# schematicEagle.net
KiCad netlist of a schematic drawn in EAGLE
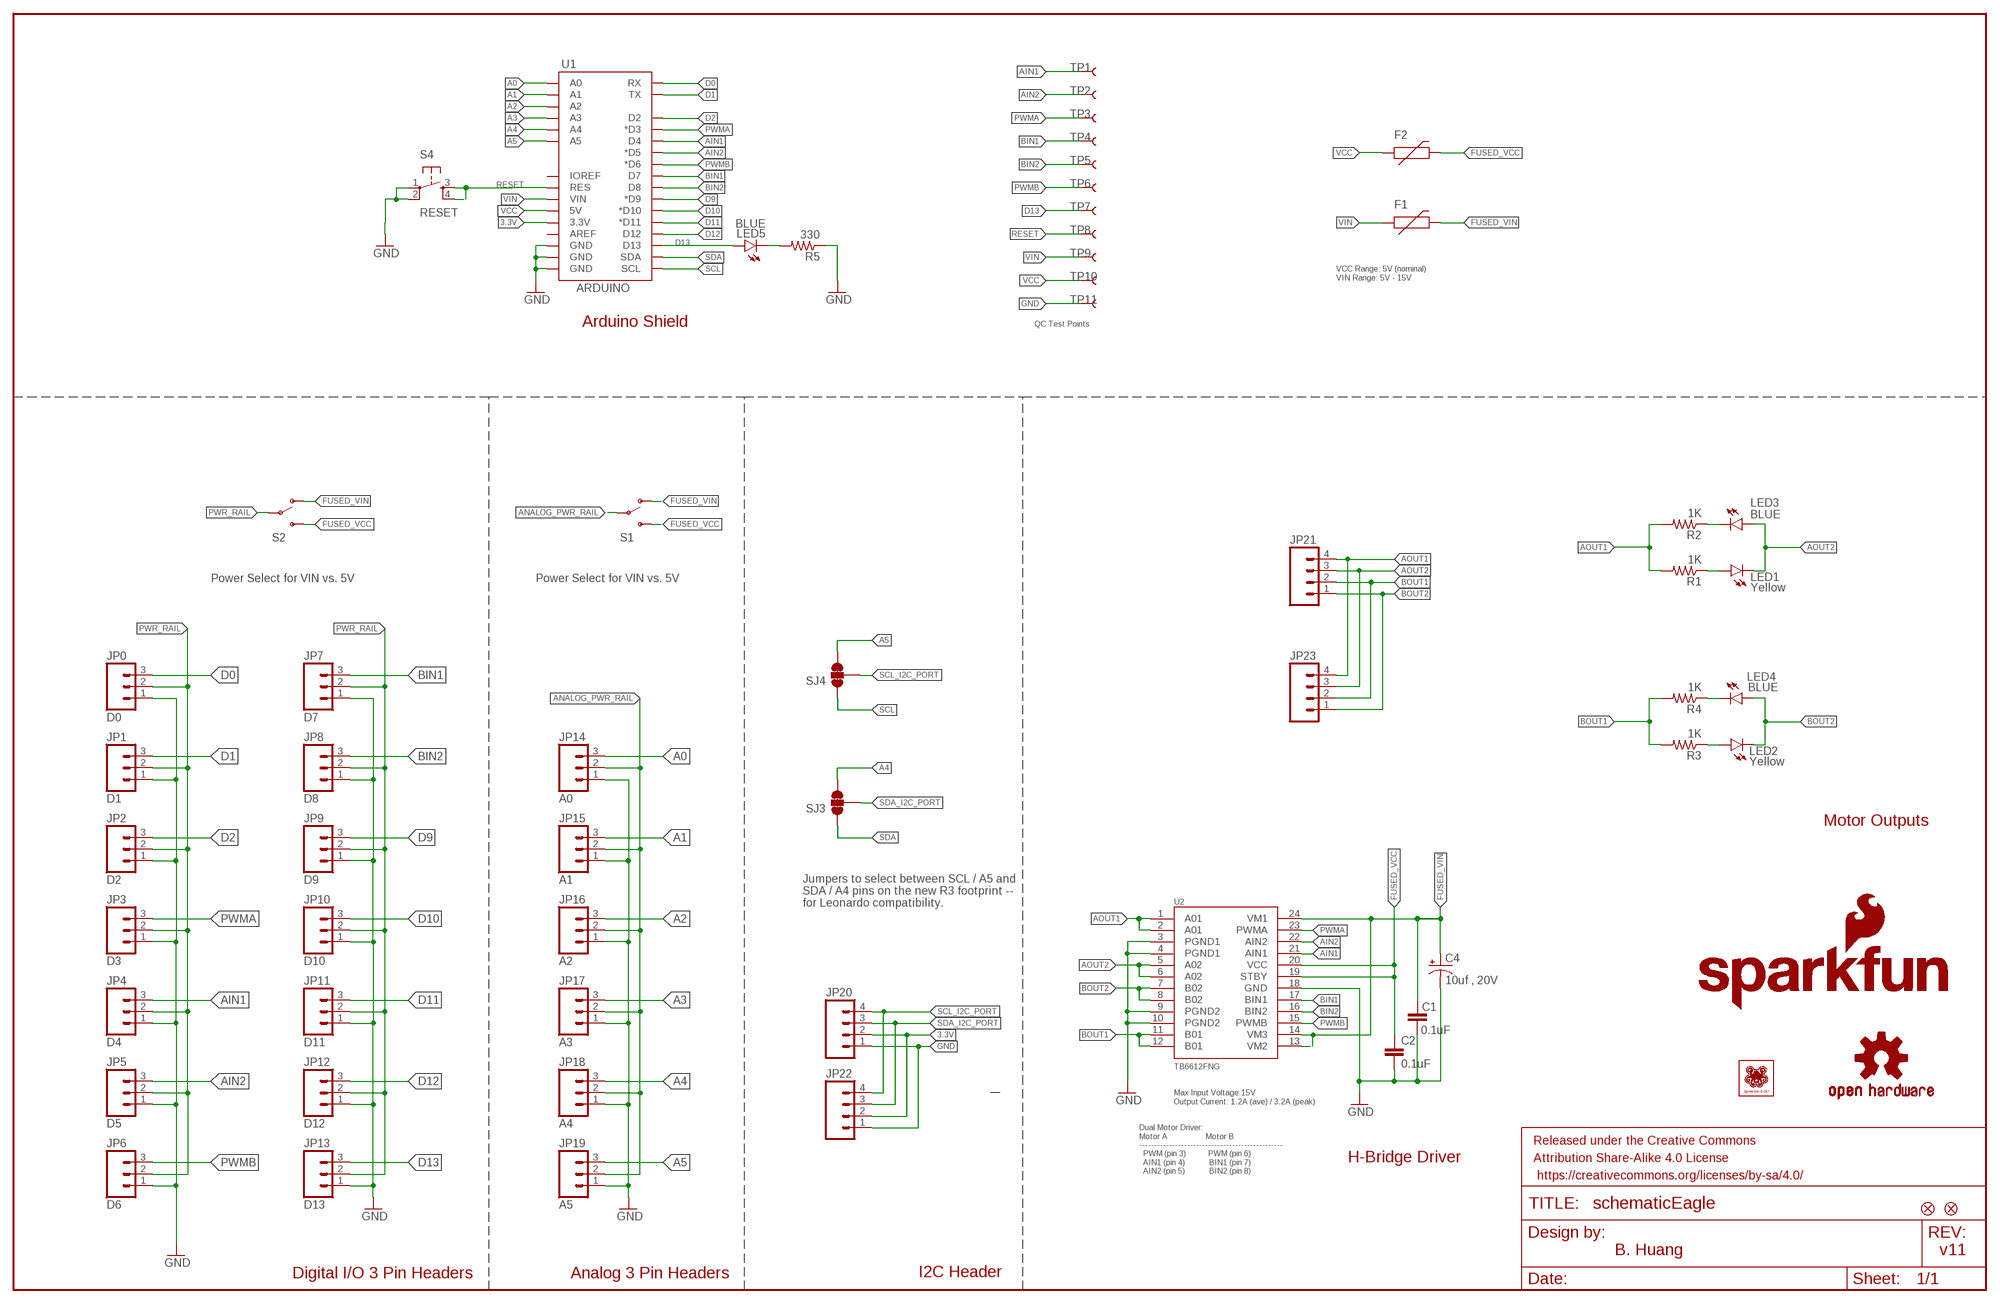
[diagram p0: schematic, sheet 1]

(export (version "E")
  (design (tool "Eeschema 10.0.6"))
  (components
    (comp (ref "C1")
      (value "0.1uF")
      (footprint "eagle-import:0603-CAP")
      (libsource (lib "eagle-import") (part "0.1UF-25V-5%(0603)"))
    )
    (comp (ref "C2")
      (value "0.1uF")
      (footprint "eagle-import:0603-CAP")
      (libsource (lib "eagle-import") (part "0.1UF-25V-5%(0603)"))
    )
    (comp (ref "C4")
      (value "10uf , 20V")
      (footprint "eagle-import:EIA3528")
      (libsource (lib "eagle-import") (part "10UF-20V-10%(TANT)"))
    )
    (comp (ref "F1")
      (value "PTCSMD")
      (footprint "eagle-import:PTC-1206")
      (libsource (lib "eagle-import") (part "PTCSMD"))
    )
    (comp (ref "F2")
      (value "PTCSMD")
      (footprint "eagle-import:PTC-1206")
      (libsource (lib "eagle-import") (part "PTCSMD"))
    )
    (comp (ref "FID1")
      (value "FIDUCIAL1X2")
      (footprint "eagle-import:FIDUCIAL-1X2")
      (libsource (lib "eagle-import") (part "FIDUCIAL1X2"))
    )
    (comp (ref "FID2")
      (value "FIDUCIAL1X2")
      (footprint "eagle-import:FIDUCIAL-1X2")
      (libsource (lib "eagle-import") (part "FIDUCIAL1X2"))
    )
    (comp (ref "FRAME2")
      (value "FRAME-LEDGER")
      (footprint "eagle-import:CREATIVE_COMMONS")
      (libsource (lib "eagle-import") (part "FRAME-LEDGER"))
    )
    (comp (ref "JP0")
      (value "D0")
      (footprint "eagle-import:1X03_LOCK")
      (libsource (lib "eagle-import") (part "M03LOCK"))
    )
    (comp (ref "JP1")
      (value "D1")
      (footprint "eagle-import:1X03_LOCK")
      (libsource (lib "eagle-import") (part "M03LOCK"))
    )
    (comp (ref "JP2")
      (value "D2")
      (footprint "eagle-import:1X03_LOCK")
      (libsource (lib "eagle-import") (part "M03LOCK"))
    )
    (comp (ref "JP3")
      (value "D3")
      (footprint "eagle-import:1X03_LOCK")
      (libsource (lib "eagle-import") (part "M03LOCK"))
    )
    (comp (ref "JP4")
      (value "D4")
      (footprint "eagle-import:1X03_LOCK")
      (libsource (lib "eagle-import") (part "M03LOCK"))
    )
    (comp (ref "JP5")
      (value "D5")
      (footprint "eagle-import:1X03_LOCK")
      (libsource (lib "eagle-import") (part "M03LOCK"))
    )
    (comp (ref "JP6")
      (value "D6")
      (footprint "eagle-import:1X03_LOCK")
      (libsource (lib "eagle-import") (part "M03LOCK"))
    )
    (comp (ref "JP7")
      (value "D7")
      (footprint "eagle-import:1X03_LOCK")
      (libsource (lib "eagle-import") (part "M03LOCK"))
    )
    (comp (ref "JP8")
      (value "D8")
      (footprint "eagle-import:1X03_LOCK")
      (libsource (lib "eagle-import") (part "M03LOCK"))
    )
    (comp (ref "JP9")
      (value "D9")
      (footprint "eagle-import:1X03_LOCK")
      (libsource (lib "eagle-import") (part "M03LOCK"))
    )
    (comp (ref "JP10")
      (value "D10")
      (footprint "eagle-import:1X03_LOCK")
      (libsource (lib "eagle-import") (part "M03LOCK"))
    )
    (comp (ref "JP11")
      (value "D11")
      (footprint "eagle-import:1X03_LOCK")
      (libsource (lib "eagle-import") (part "M03LOCK"))
    )
    (comp (ref "JP12")
      (value "D12")
      (footprint "eagle-import:1X03_LOCK")
      (libsource (lib "eagle-import") (part "M03LOCK"))
    )
    (comp (ref "JP13")
      (value "D13")
      (footprint "eagle-import:1X03_LOCK")
      (libsource (lib "eagle-import") (part "M03LOCK"))
    )
    (comp (ref "JP14")
      (value "A0")
      (footprint "eagle-import:1X03_LOCK")
      (libsource (lib "eagle-import") (part "M03LOCK"))
    )
    (comp (ref "JP15")
      (value "A1")
      (footprint "eagle-import:1X03_LOCK")
      (libsource (lib "eagle-import") (part "M03LOCK"))
    )
    (comp (ref "JP16")
      (value "A2")
      (footprint "eagle-import:1X03_LOCK")
      (libsource (lib "eagle-import") (part "M03LOCK"))
    )
    (comp (ref "JP17")
      (value "A3")
      (footprint "eagle-import:1X03_LOCK")
      (libsource (lib "eagle-import") (part "M03LOCK"))
    )
    (comp (ref "JP18")
      (value "A4")
      (footprint "eagle-import:1X03_LOCK")
      (libsource (lib "eagle-import") (part "M03LOCK"))
    )
    (comp (ref "JP19")
      (value "A5")
      (footprint "eagle-import:1X03_LOCK")
      (libsource (lib "eagle-import") (part "M03LOCK"))
    )
    (comp (ref "JP20")
      (value "M04PTH")
      (footprint "eagle-import:1X04")
      (libsource (lib "eagle-import") (part "M04PTH"))
    )
    (comp (ref "JP21")
      (value "M04PTH")
      (footprint "eagle-import:1X04")
      (libsource (lib "eagle-import") (part "M04PTH"))
    )
    (comp (ref "JP22")
      (value "M04LOCK")
      (footprint "eagle-import:1X04_LOCK")
      (libsource (lib "eagle-import") (part "M04LOCK"))
    )
    (comp (ref "JP23")
      (value "M04LOCK")
      (footprint "eagle-import:1X04_LOCK")
      (libsource (lib "eagle-import") (part "M04LOCK"))
    )
    (comp (ref "LED1")
      (value "Yellow")
      (footprint "eagle-import:LED-0603")
      (libsource (lib "eagle-import") (part "LED-YELLOW0603"))
    )
    (comp (ref "LED2")
      (value "Yellow")
      (footprint "eagle-import:LED-0603")
      (libsource (lib "eagle-import") (part "LED-YELLOW0603"))
    )
    (comp (ref "LED3")
      (value "BLUE")
      (footprint "eagle-import:LED-0603")
      (libsource (lib "eagle-import") (part "LED-BLUE0603"))
    )
    (comp (ref "LED4")
      (value "BLUE")
      (footprint "eagle-import:LED-0603")
      (libsource (lib "eagle-import") (part "LED-BLUE0603"))
    )
    (comp (ref "LED5")
      (value "BLUE")
      (footprint "eagle-import:LED-0603")
      (libsource (lib "eagle-import") (part "LED-BLUE0603"))
    )
    (comp (ref "LOGO1")
      (value "OSHW-LOGOM")
      (footprint "eagle-import:OSHW-LOGO-M")
      (libsource (lib "eagle-import") (part "OSHW-LOGOM"))
    )
    (comp (ref "LOGO2")
      (value "SFE_LOGO_NAME_FLAME.1_INCH")
      (footprint "eagle-import:SFE_LOGO_NAME_FLAME_.1")
      (libsource (lib "eagle-import") (part "SFE_LOGO_NAME_FLAME.1_INCH"))
    )
    (comp (ref "LOGO3")
      (value "SFE_LOGO_FLAME.2COP")
      (footprint "eagle-import:SFE_LOGO_FLAME_COPPER_.2")
      (libsource (lib "eagle-import") (part "SFE_LOGO_FLAME.2COP"))
    )
    (comp (ref "LOGO4")
      (value "SFE_LOGO_NAME_FLAME.1_INCH")
      (footprint "eagle-import:SFE_LOGO_NAME_FLAME_.1")
      (libsource (lib "eagle-import") (part "SFE_LOGO_NAME_FLAME.1_INCH"))
    )
    (comp (ref "R1")
      (value "1K")
      (footprint "eagle-import:0603-RES")
      (libsource (lib "eagle-import") (part "1KOHM-1/10W-1%(0603)"))
    )
    (comp (ref "R2")
      (value "1K")
      (footprint "eagle-import:0603-RES")
      (libsource (lib "eagle-import") (part "1KOHM-1/10W-1%(0603)"))
    )
    (comp (ref "R3")
      (value "1K")
      (footprint "eagle-import:0603-RES")
      (libsource (lib "eagle-import") (part "1KOHM-1/10W-1%(0603)"))
    )
    (comp (ref "R4")
      (value "1K")
      (footprint "eagle-import:0603-RES")
      (libsource (lib "eagle-import") (part "1KOHM-1/10W-1%(0603)"))
    )
    (comp (ref "R5")
      (value "330")
      (footprint "eagle-import:0603-RES")
      (libsource (lib "eagle-import") (part "330OHM1/10W1%(0603)"))
    )
    (comp (ref "S1")
      (value "SWITCH-SPDTSMD")
      (footprint "eagle-import:AYZ0202")
      (libsource (lib "eagle-import") (part "SWITCH-SPDTSMD"))
    )
    (comp (ref "S2")
      (value "SWITCH-SPDTSMD")
      (footprint "eagle-import:AYZ0202")
      (libsource (lib "eagle-import") (part "SWITCH-SPDTSMD"))
    )
    (comp (ref "S4")
      (value "RESET")
      (footprint "eagle-import:TACTILE-SWITCH-SMD")
      (libsource (lib "eagle-import") (part "TAC_SWITCHSMD"))
    )
    (comp (ref "SJ3")
      (value "JUMPER-PAD-3-NC_BY_TRACE")
      (footprint "eagle-import:PAD-JUMPER-3-3OF3_NC_BY_TRACE_YES_SILK_FULL_BOX")
      (libsource (lib "eagle-import") (part "JUMPER-PAD-3-NC_BY_TRACE"))
    )
    (comp (ref "SJ4")
      (value "JUMPER-PAD-3-NC_BY_TRACE")
      (footprint "eagle-import:PAD-JUMPER-3-3OF3_NC_BY_TRACE_YES_SILK_FULL_BOX")
      (libsource (lib "eagle-import") (part "JUMPER-PAD-3-NC_BY_TRACE"))
    )
    (comp (ref "TP1")
      (value "TEST-POINT3X5")
      (footprint "eagle-import:PAD.03X.05")
      (libsource (lib "eagle-import") (part "TEST-POINT3X5"))
    )
    (comp (ref "TP2")
      (value "TEST-POINT3X5")
      (footprint "eagle-import:PAD.03X.05")
      (libsource (lib "eagle-import") (part "TEST-POINT3X5"))
    )
    (comp (ref "TP3")
      (value "TEST-POINT3X5")
      (footprint "eagle-import:PAD.03X.05")
      (libsource (lib "eagle-import") (part "TEST-POINT3X5"))
    )
    (comp (ref "TP4")
      (value "TEST-POINT3X5")
      (footprint "eagle-import:PAD.03X.05")
      (libsource (lib "eagle-import") (part "TEST-POINT3X5"))
    )
    (comp (ref "TP5")
      (value "TEST-POINT3X5")
      (footprint "eagle-import:PAD.03X.05")
      (libsource (lib "eagle-import") (part "TEST-POINT3X5"))
    )
    (comp (ref "TP6")
      (value "TEST-POINT3X5")
      (footprint "eagle-import:PAD.03X.05")
      (libsource (lib "eagle-import") (part "TEST-POINT3X5"))
    )
    (comp (ref "TP7")
      (value "TEST-POINT3X5")
      (footprint "eagle-import:PAD.03X.05")
      (libsource (lib "eagle-import") (part "TEST-POINT3X5"))
    )
    (comp (ref "TP8")
      (value "TEST-POINT3X5")
      (footprint "eagle-import:PAD.03X.05")
      (libsource (lib "eagle-import") (part "TEST-POINT3X5"))
    )
    (comp (ref "TP9")
      (value "TEST-POINT3X5")
      (footprint "eagle-import:PAD.03X.05")
      (libsource (lib "eagle-import") (part "TEST-POINT3X5"))
    )
    (comp (ref "TP10")
      (value "TEST-POINT3X5")
      (footprint "eagle-import:PAD.03X.05")
      (libsource (lib "eagle-import") (part "TEST-POINT3X5"))
    )
    (comp (ref "TP11")
      (value "TEST-POINT3X5")
      (footprint "eagle-import:PAD.03X.05")
      (libsource (lib "eagle-import") (part "TEST-POINT3X5"))
    )
    (comp (ref "U$1")
      (value "SFE_LUDUSSFE_LUDUS-M")
      (footprint "eagle-import:SFE_LUDUS-M")
      (libsource (lib "eagle-import") (part "SFE_LUDUSSFE_LUDUS-M"))
    )
    (comp (ref "U1")
      (value "ARDUINO")
      (footprint "eagle-import:UNO_R3_SHIELD_NOLABELS_LOCK")
      (libsource (lib "eagle-import") (part "ARDUINO_R3_SHIELDUNO_R3_SHIELD_NOLABELS_LOCK"))
    )
    (comp (ref "U2")
      (value "TB6612FNG")
      (footprint "eagle-import:SSOP24")
      (libsource (lib "eagle-import") (part "TB6612FNG"))
    )
  )
  (nets
    (net (code "1") (name "3.3V") (class "Default")
      (node (ref "JP20") (pin "2") (pinfunction "2_2") (pintype "passive"))
      (node (ref "JP22") (pin "2") (pinfunction "2_2") (pintype "passive"))
      (node (ref "U1") (pin "3.3V") (pinfunction "3.3V_3.3V") (pintype "bidirectional"))
    )
    (net (code "2") (name "A0") (class "Default")
      (node (ref "JP14") (pin "3") (pinfunction "3_3") (pintype "passive"))
      (node (ref "U1") (pin "A0") (pinfunction "A0_A0") (pintype "bidirectional"))
    )
    (net (code "3") (name "A1") (class "Default")
      (node (ref "JP15") (pin "3") (pinfunction "3_3") (pintype "passive"))
      (node (ref "U1") (pin "A1") (pinfunction "A1_A1") (pintype "bidirectional"))
    )
    (net (code "4") (name "A2") (class "Default")
      (node (ref "JP16") (pin "3") (pinfunction "3_3") (pintype "passive"))
      (node (ref "U1") (pin "A2") (pinfunction "A2_A2") (pintype "bidirectional"))
    )
    (net (code "5") (name "A3") (class "Default")
      (node (ref "JP17") (pin "3") (pinfunction "3_3") (pintype "passive"))
      (node (ref "U1") (pin "A3") (pinfunction "A3_A3") (pintype "bidirectional"))
    )
    (net (code "6") (name "A4") (class "Default")
      (node (ref "JP18") (pin "3") (pinfunction "3_3") (pintype "passive"))
      (node (ref "SJ3") (pin "3") (pinfunction "3_3") (pintype "passive"))
      (node (ref "U1") (pin "A4") (pinfunction "A4_A4") (pintype "bidirectional"))
    )
    (net (code "7") (name "A5") (class "Default")
      (node (ref "JP19") (pin "3") (pinfunction "3_3") (pintype "passive"))
      (node (ref "SJ4") (pin "3") (pinfunction "3_3") (pintype "passive"))
      (node (ref "U1") (pin "A5") (pinfunction "A5_A5") (pintype "bidirectional"))
    )
    (net (code "8") (name "AIN1") (class "Default")
      (node (ref "JP4") (pin "3") (pinfunction "3_3") (pintype "passive"))
      (node (ref "TP1") (pin "P$1") (pinfunction "1_P$1") (pintype "bidirectional"))
      (node (ref "U1") (pin "D4") (pinfunction "D4_D4") (pintype "bidirectional"))
      (node (ref "U2") (pin "21") (pinfunction "AIN1_21") (pintype "bidirectional"))
    )
    (net (code "9") (name "AIN2") (class "Default")
      (node (ref "JP5") (pin "3") (pinfunction "3_3") (pintype "passive"))
      (node (ref "TP2") (pin "P$1") (pinfunction "1_P$1") (pintype "bidirectional"))
      (node (ref "U1") (pin "D5") (pinfunction "*D5_D5") (pintype "bidirectional"))
      (node (ref "U2") (pin "22") (pinfunction "AIN2_22") (pintype "bidirectional"))
    )
    (net (code "10") (name "ANALOG_PWR_RAIL") (class "Default")
      (node (ref "JP14") (pin "2") (pinfunction "2_2") (pintype "passive"))
      (node (ref "JP15") (pin "2") (pinfunction "2_2") (pintype "passive"))
      (node (ref "JP16") (pin "2") (pinfunction "2_2") (pintype "passive"))
      (node (ref "JP17") (pin "2") (pinfunction "2_2") (pintype "passive"))
      (node (ref "JP18") (pin "2") (pinfunction "2_2") (pintype "passive"))
      (node (ref "JP19") (pin "2") (pinfunction "2_2") (pintype "passive"))
      (node (ref "S1") (pin "2") (pinfunction "P_2") (pintype "passive"))
    )
    (net (code "11") (name "AOUT1") (class "Default")
      (node (ref "JP21") (pin "4") (pinfunction "4_4") (pintype "passive"))
      (node (ref "JP23") (pin "4") (pinfunction "4_4") (pintype "passive"))
      (node (ref "R1") (pin "2") (pinfunction "2_2") (pintype "passive"))
      (node (ref "R2") (pin "2") (pinfunction "2_2") (pintype "passive"))
      (node (ref "U2") (pin "1") (pinfunction "A01_1") (pintype "bidirectional"))
      (node (ref "U2") (pin "2") (pinfunction "A01_2") (pintype "bidirectional"))
    )
    (net (code "12") (name "AOUT2") (class "Default")
      (node (ref "JP21") (pin "3") (pinfunction "3_3") (pintype "passive"))
      (node (ref "JP23") (pin "3") (pinfunction "3_3") (pintype "passive"))
      (node (ref "LED1") (pin "C") (pinfunction "C_C") (pintype "passive"))
      (node (ref "LED3") (pin "A") (pinfunction "A_A") (pintype "passive"))
      (node (ref "U2") (pin "5") (pinfunction "A02_5") (pintype "bidirectional"))
      (node (ref "U2") (pin "6") (pinfunction "A02_6") (pintype "bidirectional"))
    )
    (net (code "13") (name "BIN1") (class "Default")
      (node (ref "JP7") (pin "3") (pinfunction "3_3") (pintype "passive"))
      (node (ref "TP4") (pin "P$1") (pinfunction "1_P$1") (pintype "bidirectional"))
      (node (ref "U1") (pin "D7") (pinfunction "D7_D7") (pintype "bidirectional"))
      (node (ref "U2") (pin "17") (pinfunction "BIN1_17") (pintype "bidirectional"))
    )
    (net (code "14") (name "BIN2") (class "Default")
      (node (ref "JP8") (pin "3") (pinfunction "3_3") (pintype "passive"))
      (node (ref "TP5") (pin "P$1") (pinfunction "1_P$1") (pintype "bidirectional"))
      (node (ref "U1") (pin "D8") (pinfunction "D8_D8") (pintype "bidirectional"))
      (node (ref "U2") (pin "16") (pinfunction "BIN2_16") (pintype "bidirectional"))
    )
    (net (code "15") (name "BOUT1") (class "Default")
      (node (ref "JP21") (pin "2") (pinfunction "2_2") (pintype "passive"))
      (node (ref "JP23") (pin "2") (pinfunction "2_2") (pintype "passive"))
      (node (ref "R3") (pin "2") (pinfunction "2_2") (pintype "passive"))
      (node (ref "R4") (pin "2") (pinfunction "2_2") (pintype "passive"))
      (node (ref "U2") (pin "11") (pinfunction "B01_11") (pintype "bidirectional"))
      (node (ref "U2") (pin "12") (pinfunction "B01_12") (pintype "bidirectional"))
    )
    (net (code "16") (name "BOUT2") (class "Default")
      (node (ref "JP21") (pin "1") (pinfunction "1_1") (pintype "passive"))
      (node (ref "JP23") (pin "1") (pinfunction "1_1") (pintype "passive"))
      (node (ref "LED2") (pin "C") (pinfunction "C_C") (pintype "passive"))
      (node (ref "LED4") (pin "A") (pinfunction "A_A") (pintype "passive"))
      (node (ref "U2") (pin "7") (pinfunction "B02_7") (pintype "bidirectional"))
      (node (ref "U2") (pin "8") (pinfunction "B02_8") (pintype "bidirectional"))
    )
    (net (code "17") (name "D0") (class "Default")
      (node (ref "JP0") (pin "3") (pinfunction "3_3") (pintype "passive"))
      (node (ref "U1") (pin "RX") (pinfunction "RX_RX") (pintype "bidirectional"))
    )
    (net (code "18") (name "D1") (class "Default")
      (node (ref "JP1") (pin "3") (pinfunction "3_3") (pintype "passive"))
      (node (ref "U1") (pin "TX") (pinfunction "TX_TX") (pintype "bidirectional"))
    )
    (net (code "19") (name "D2") (class "Default")
      (node (ref "JP2") (pin "3") (pinfunction "3_3") (pintype "passive"))
      (node (ref "U1") (pin "D2") (pinfunction "D2_D2") (pintype "bidirectional"))
    )
    (net (code "20") (name "D9") (class "Default")
      (node (ref "JP9") (pin "3") (pinfunction "3_3") (pintype "passive"))
      (node (ref "U1") (pin "D9") (pinfunction "*D9_D9") (pintype "bidirectional"))
    )
    (net (code "21") (name "D10") (class "Default")
      (node (ref "JP10") (pin "3") (pinfunction "3_3") (pintype "passive"))
      (node (ref "U1") (pin "D10") (pinfunction "*D10_D10") (pintype "bidirectional"))
    )
    (net (code "22") (name "D11") (class "Default")
      (node (ref "JP11") (pin "3") (pinfunction "3_3") (pintype "passive"))
      (node (ref "U1") (pin "D11") (pinfunction "*D11_D11") (pintype "bidirectional"))
    )
    (net (code "23") (name "D12") (class "Default")
      (node (ref "JP12") (pin "3") (pinfunction "3_3") (pintype "passive"))
      (node (ref "U1") (pin "D12") (pinfunction "D12_D12") (pintype "bidirectional"))
    )
    (net (code "24") (name "D13") (class "Default")
      (node (ref "JP13") (pin "3") (pinfunction "3_3") (pintype "passive"))
      (node (ref "LED5") (pin "A") (pinfunction "A_A") (pintype "passive"))
      (node (ref "TP7") (pin "P$1") (pinfunction "1_P$1") (pintype "bidirectional"))
      (node (ref "U1") (pin "D13") (pinfunction "D13_D13") (pintype "bidirectional"))
    )
    (net (code "25") (name "FUSED_VCC") (class "Default")
      (node (ref "C2") (pin "1") (pinfunction "1_1") (pintype "passive"))
      (node (ref "F2") (pin "2") (pinfunction "2_2") (pintype "bidirectional"))
      (node (ref "S1") (pin "3") (pinfunction "S_3") (pintype "passive"))
      (node (ref "S2") (pin "3") (pinfunction "S_3") (pintype "passive"))
      (node (ref "U2") (pin "19") (pinfunction "STBY_19") (pintype "bidirectional"))
      (node (ref "U2") (pin "20") (pinfunction "VCC_20") (pintype "bidirectional"))
    )
    (net (code "26") (name "FUSED_VIN") (class "Default")
      (node (ref "C1") (pin "1") (pinfunction "1_1") (pintype "passive"))
      (node (ref "C4") (pin "A") (pinfunction "+_A") (pintype "passive"))
      (node (ref "F1") (pin "2") (pinfunction "2_2") (pintype "bidirectional"))
      (node (ref "S1") (pin "1") (pinfunction "O_1") (pintype "passive"))
      (node (ref "S2") (pin "1") (pinfunction "O_1") (pintype "passive"))
      (node (ref "U2") (pin "13") (pinfunction "VM2_13") (pintype "bidirectional"))
      (node (ref "U2") (pin "14") (pinfunction "VM3_14") (pintype "bidirectional"))
      (node (ref "U2") (pin "24") (pinfunction "VM1_24") (pintype "bidirectional"))
    )
    (net (code "27") (name "GND") (class "Default")
      (node (ref "C1") (pin "2") (pinfunction "2_2") (pintype "passive"))
      (node (ref "C2") (pin "2") (pinfunction "2_2") (pintype "passive"))
      (node (ref "C4") (pin "C") (pinfunction "-_C") (pintype "passive"))
      (node (ref "JP0") (pin "1") (pinfunction "1_1") (pintype "passive"))
      (node (ref "JP1") (pin "1") (pinfunction "1_1") (pintype "passive"))
      (node (ref "JP10") (pin "1") (pinfunction "1_1") (pintype "passive"))
      (node (ref "JP11") (pin "1") (pinfunction "1_1") (pintype "passive"))
      (node (ref "JP12") (pin "1") (pinfunction "1_1") (pintype "passive"))
      (node (ref "JP13") (pin "1") (pinfunction "1_1") (pintype "passive"))
      (node (ref "JP14") (pin "1") (pinfunction "1_1") (pintype "passive"))
      (node (ref "JP15") (pin "1") (pinfunction "1_1") (pintype "passive"))
      (node (ref "JP16") (pin "1") (pinfunction "1_1") (pintype "passive"))
      (node (ref "JP17") (pin "1") (pinfunction "1_1") (pintype "passive"))
      (node (ref "JP18") (pin "1") (pinfunction "1_1") (pintype "passive"))
      (node (ref "JP19") (pin "1") (pinfunction "1_1") (pintype "passive"))
      (node (ref "JP2") (pin "1") (pinfunction "1_1") (pintype "passive"))
      (node (ref "JP20") (pin "1") (pinfunction "1_1") (pintype "passive"))
      (node (ref "JP22") (pin "1") (pinfunction "1_1") (pintype "passive"))
      (node (ref "JP3") (pin "1") (pinfunction "1_1") (pintype "passive"))
      (node (ref "JP4") (pin "1") (pinfunction "1_1") (pintype "passive"))
      (node (ref "JP5") (pin "1") (pinfunction "1_1") (pintype "passive"))
      (node (ref "JP6") (pin "1") (pinfunction "1_1") (pintype "passive"))
      (node (ref "JP7") (pin "1") (pinfunction "1_1") (pintype "passive"))
      (node (ref "JP8") (pin "1") (pinfunction "1_1") (pintype "passive"))
      (node (ref "JP9") (pin "1") (pinfunction "1_1") (pintype "passive"))
      (node (ref "R5") (pin "1") (pinfunction "1_1") (pintype "passive"))
      (node (ref "S4") (pin "1") (pinfunction "1_1") (pintype "passive"))
      (node (ref "S4") (pin "2") (pinfunction "2_2") (pintype "passive"))
      (node (ref "TP11") (pin "P$1") (pinfunction "1_P$1") (pintype "bidirectional"))
      (node (ref "U1") (pin "GND@0") (pinfunction "GND_GND@0") (pintype "bidirectional"))
      (node (ref "U1") (pin "GND@1") (pinfunction "GND_GND@1") (pintype "bidirectional"))
      (node (ref "U1") (pin "GND@2") (pinfunction "GND_GND@2") (pintype "bidirectional"))
      (node (ref "U2") (pin "10") (pinfunction "PGND2_10") (pintype "bidirectional"))
      (node (ref "U2") (pin "18") (pinfunction "GND_18") (pintype "bidirectional"))
      (node (ref "U2") (pin "3") (pinfunction "PGND1_3") (pintype "bidirectional"))
      (node (ref "U2") (pin "4") (pinfunction "PGND1_4") (pintype "bidirectional"))
      (node (ref "U2") (pin "9") (pinfunction "PGND2_9") (pintype "bidirectional"))
    )
    (net (code "28") (name "Net-(LED1-PadA)") (class "Default")
      (node (ref "LED1") (pin "A") (pinfunction "A_A") (pintype "passive"))
      (node (ref "R1") (pin "1") (pinfunction "1_1") (pintype "passive"))
    )
    (net (code "29") (name "Net-(LED2-PadA)") (class "Default")
      (node (ref "LED2") (pin "A") (pinfunction "A_A") (pintype "passive"))
      (node (ref "R3") (pin "1") (pinfunction "1_1") (pintype "passive"))
    )
    (net (code "30") (name "Net-(LED3-PadC)") (class "Default")
      (node (ref "LED3") (pin "C") (pinfunction "C_C") (pintype "passive"))
      (node (ref "R2") (pin "1") (pinfunction "1_1") (pintype "passive"))
    )
    (net (code "31") (name "Net-(LED4-PadC)") (class "Default")
      (node (ref "LED4") (pin "C") (pinfunction "C_C") (pintype "passive"))
      (node (ref "R4") (pin "1") (pinfunction "1_1") (pintype "passive"))
    )
    (net (code "32") (name "Net-(LED5-PadC)") (class "Default")
      (node (ref "LED5") (pin "C") (pinfunction "C_C") (pintype "passive"))
      (node (ref "R5") (pin "2") (pinfunction "2_2") (pintype "passive"))
    )
    (net (code "33") (name "PWMA") (class "Default")
      (node (ref "JP3") (pin "3") (pinfunction "3_3") (pintype "passive"))
      (node (ref "TP3") (pin "P$1") (pinfunction "1_P$1") (pintype "bidirectional"))
      (node (ref "U1") (pin "D3") (pinfunction "*D3_D3") (pintype "bidirectional"))
      (node (ref "U2") (pin "23") (pinfunction "PWMA_23") (pintype "bidirectional"))
    )
    (net (code "34") (name "PWMB") (class "Default")
      (node (ref "JP6") (pin "3") (pinfunction "3_3") (pintype "passive"))
      (node (ref "TP6") (pin "P$1") (pinfunction "1_P$1") (pintype "bidirectional"))
      (node (ref "U1") (pin "D6") (pinfunction "*D6_D6") (pintype "bidirectional"))
      (node (ref "U2") (pin "15") (pinfunction "PWMB_15") (pintype "bidirectional"))
    )
    (net (code "35") (name "PWR_RAIL") (class "Default")
      (node (ref "JP0") (pin "2") (pinfunction "2_2") (pintype "passive"))
      (node (ref "JP1") (pin "2") (pinfunction "2_2") (pintype "passive"))
      (node (ref "JP10") (pin "2") (pinfunction "2_2") (pintype "passive"))
      (node (ref "JP11") (pin "2") (pinfunction "2_2") (pintype "passive"))
      (node (ref "JP12") (pin "2") (pinfunction "2_2") (pintype "passive"))
      (node (ref "JP13") (pin "2") (pinfunction "2_2") (pintype "passive"))
      (node (ref "JP2") (pin "2") (pinfunction "2_2") (pintype "passive"))
      (node (ref "JP3") (pin "2") (pinfunction "2_2") (pintype "passive"))
      (node (ref "JP4") (pin "2") (pinfunction "2_2") (pintype "passive"))
      (node (ref "JP5") (pin "2") (pinfunction "2_2") (pintype "passive"))
      (node (ref "JP6") (pin "2") (pinfunction "2_2") (pintype "passive"))
      (node (ref "JP7") (pin "2") (pinfunction "2_2") (pintype "passive"))
      (node (ref "JP8") (pin "2") (pinfunction "2_2") (pintype "passive"))
      (node (ref "JP9") (pin "2") (pinfunction "2_2") (pintype "passive"))
      (node (ref "S2") (pin "2") (pinfunction "P_2") (pintype "passive"))
    )
    (net (code "36") (name "RESET") (class "Default")
      (node (ref "S4") (pin "3") (pinfunction "3_3") (pintype "passive"))
      (node (ref "S4") (pin "4") (pinfunction "4_4") (pintype "passive"))
      (node (ref "TP8") (pin "P$1") (pinfunction "1_P$1") (pintype "bidirectional"))
      (node (ref "U1") (pin "RES") (pinfunction "RES_RES") (pintype "bidirectional"))
    )
    (net (code "37") (name "SCL") (class "Default")
      (node (ref "SJ4") (pin "1") (pinfunction "1_1") (pintype "passive"))
      (node (ref "U1") (pin "SCL") (pinfunction "SCL_SCL") (pintype "bidirectional"))
    )
    (net (code "38") (name "SCL_I2C_PORT") (class "Default")
      (node (ref "JP20") (pin "4") (pinfunction "4_4") (pintype "passive"))
      (node (ref "JP22") (pin "4") (pinfunction "4_4") (pintype "passive"))
      (node (ref "SJ4") (pin "2") (pinfunction "2_2") (pintype "passive"))
    )
    (net (code "39") (name "SDA") (class "Default")
      (node (ref "SJ3") (pin "1") (pinfunction "1_1") (pintype "passive"))
      (node (ref "U1") (pin "SDA") (pinfunction "SDA_SDA") (pintype "bidirectional"))
    )
    (net (code "40") (name "SDA_I2C_PORT") (class "Default")
      (node (ref "JP20") (pin "3") (pinfunction "3_3") (pintype "passive"))
      (node (ref "JP22") (pin "3") (pinfunction "3_3") (pintype "passive"))
      (node (ref "SJ3") (pin "2") (pinfunction "2_2") (pintype "passive"))
    )
    (net (code "41") (name "VCC") (class "Default")
      (node (ref "F2") (pin "1") (pinfunction "1_1") (pintype "bidirectional"))
      (node (ref "TP10") (pin "P$1") (pinfunction "1_P$1") (pintype "bidirectional"))
      (node (ref "U1") (pin "5V") (pinfunction "5V_5V") (pintype "bidirectional"))
    )
    (net (code "42") (name "VIN") (class "Default")
      (node (ref "F1") (pin "1") (pinfunction "1_1") (pintype "bidirectional"))
      (node (ref "TP9") (pin "P$1") (pinfunction "1_P$1") (pintype "bidirectional"))
      (node (ref "U1") (pin "VIN") (pinfunction "VIN_VIN") (pintype "bidirectional"))
    )
    (net (code "43") (name "unconnected-(U1-PadAREF)") (class "Default")
      (node (ref "U1") (pin "AREF") (pinfunction "AREF_AREF") (pintype "bidirectional"))
    )
    (net (code "44") (name "unconnected-(U1-PadIOREF)") (class "Default")
      (node (ref "U1") (pin "IOREF") (pinfunction "IOREF_IOREF") (pintype "bidirectional"))
    )
  )
)
